# MCISO-S07-V00-CANMain.net
KiCad netlist of a schematic drawn in Altium Designer
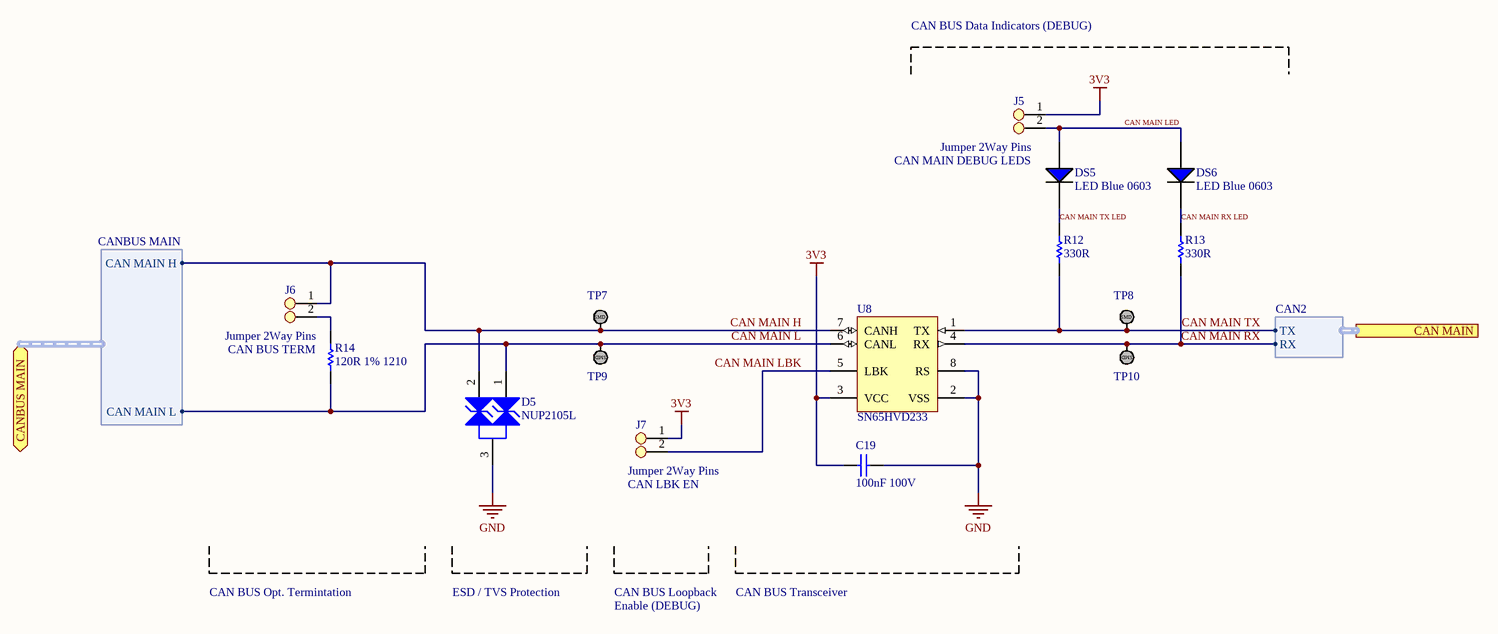
[diagram p0: MCISO-S07-V00-CANMain.SchDoc]

(export (version "E")
  (design (tool "Eeschema 10.0.6"))
  (components
    (comp (ref "C19")
      (value "100nF 100V")
      (footprint "Cap_Ceramic_0603")
      (description "Capacitor, Ceramic, SMD, 100nF, 100V, 5%, X7R, 0603")
      (libsource (lib "StandardCapacitors") (part "100nF 100V 5% X7R 0603"))
    )
    (comp (ref "D5")
      (value "NUP2105L")
      (footprint "NUP2105L")
      (libsource (lib "QUTMS_CANLibrary") (part "NUP2105L"))
    )
    (comp (ref "DS5")
      (value "LED Blue 0603")
      (footprint "LED BLUE 0603")
      (libsource (lib "QUTMS_LEDLibrary") (part "LED BLUE 0603"))
    )
    (comp (ref "DS6")
      (value "LED Blue 0603")
      (footprint "LED BLUE 0603")
      (libsource (lib "QUTMS_LEDLibrary") (part "LED BLUE 0603"))
    )
    (comp (ref "J5")
      (value "Jumper 2Way Pins")
      (footprint "Jumper_2Way_Pin")
      (description "Jumper 2Way Side Pins")
      (libsource (lib "QUTMS_JumperLibrary") (part "Jumper 2Way Side Pins"))
    )
    (comp (ref "J6")
      (value "Jumper 2Way Pins")
      (footprint "Jumper_2Way_Pin")
      (description "Jumper 2Way Side Pins")
      (libsource (lib "QUTMS_JumperLibrary") (part "Jumper 2Way Side Pins"))
    )
    (comp (ref "J7")
      (value "Jumper 2Way Pins")
      (footprint "Jumper_2Way_Pin")
      (description "Jumper 2Way Side Pins")
      (libsource (lib "QUTMS_JumperLibrary") (part "Jumper 2Way Side Pins"))
    )
    (comp (ref "R12")
      (value "330R")
      (footprint "Res_ThinFilm_0603")
      (description "Resistor, SMD, 330R, 0.1W, 5%, 0603")
      (libsource (lib "StandardResistors") (part "330R 5% 0603"))
    )
    (comp (ref "R13")
      (value "330R")
      (footprint "Res_ThinFilm_0603")
      (description "Resistor, SMD, 330R, 0.1W, 5%, 0603")
      (libsource (lib "StandardResistors") (part "330R 5% 0603"))
    )
    (comp (ref "R14")
      (value "120R 1% 1210")
      (footprint "Res_ThinFilm_1210")
      (description "Resistor, SMD, 120R, 0.25W, 1%, 1210")
      (libsource (lib "StandardResistors") (part "120R 1% 1210"))
    )
    (comp (ref "TP7")
      (value "TestPoint_SMD")
      (footprint "TestPointSMD")
      (libsource (lib "StandardTest") (part "TestPoint_SMD"))
    )
    (comp (ref "TP8")
      (value "TestPoint_SMD")
      (footprint "TestPointSMD")
      (libsource (lib "StandardTest") (part "TestPoint_SMD"))
    )
    (comp (ref "TP9")
      (value "TestPoint_SMD")
      (footprint "TestPointSMD")
      (libsource (lib "StandardTest") (part "TestPoint_SMD"))
    )
    (comp (ref "TP10")
      (value "TestPoint_SMD")
      (footprint "TestPointSMD")
      (libsource (lib "StandardTest") (part "TestPoint_SMD"))
    )
    (comp (ref "U8")
      (value "SN65HVD233")
      (footprint "SN65HVD233DR")
      (libsource (lib "QUTMS_CANLibrary") (part "SN65HVD233"))
    )
  )
  (nets
    (net (code "4") (name "/CAN MAIN H") (class "Default")
      (node (ref "D5") (pin "2") (pinfunction "2_2") (pintype "passive"))
      (node (ref "J6") (pin "1") (pinfunction "1_1") (pintype "passive"))
      (node (ref "TP7") (pin "1") (pinfunction "1_1") (pintype "passive"))
      (node (ref "U8") (pin "7") (pinfunction "CANH_7") (pintype "bidirectional"))
    )
    (net (code "5") (name "/CAN MAIN L") (class "Default")
      (node (ref "D5") (pin "1") (pinfunction "1_1") (pintype "passive"))
      (node (ref "R14") (pin "1") (pinfunction "1_1") (pintype "passive"))
      (node (ref "TP9") (pin "1") (pinfunction "1_1") (pintype "passive"))
      (node (ref "U8") (pin "6") (pinfunction "CANL_6") (pintype "bidirectional"))
    )
    (net (code "6") (name "/CAN MAIN LBK") (class "Default")
      (node (ref "J7") (pin "2") (pinfunction "2_2") (pintype "passive"))
      (node (ref "U8") (pin "5") (pinfunction "LBK_5") (pintype "passive"))
    )
    (net (code "7") (name "/CAN MAIN LED") (class "Default")
      (node (ref "DS5") (pin "1") (pinfunction "A_1") (pintype "passive"))
      (node (ref "DS6") (pin "1") (pinfunction "A_1") (pintype "passive"))
      (node (ref "J5") (pin "2") (pinfunction "2_2") (pintype "passive"))
    )
    (net (code "8") (name "/CAN MAIN RX") (class "Default")
      (node (ref "R13") (pin "1") (pinfunction "1_1") (pintype "passive"))
      (node (ref "TP10") (pin "1") (pinfunction "1_1") (pintype "passive"))
      (node (ref "U8") (pin "4") (pinfunction "RX_4") (pintype "output"))
    )
    (net (code "9") (name "/CAN MAIN RX LED") (class "Default")
      (node (ref "DS6") (pin "2") (pinfunction "C_2") (pintype "passive"))
      (node (ref "R13") (pin "2") (pinfunction "2_2") (pintype "passive"))
    )
    (net (code "10") (name "/CAN MAIN TX") (class "Default")
      (node (ref "R12") (pin "1") (pinfunction "1_1") (pintype "passive"))
      (node (ref "TP8") (pin "1") (pinfunction "1_1") (pintype "passive"))
      (node (ref "U8") (pin "1") (pinfunction "TX_1") (pintype "input"))
    )
    (net (code "11") (name "/CAN MAIN TX LED") (class "Default")
      (node (ref "DS5") (pin "2") (pinfunction "C_2") (pintype "passive"))
      (node (ref "R12") (pin "2") (pinfunction "2_2") (pintype "passive"))
    )
    (net (code "14") (name "3V3") (class "Default")
      (node (ref "C19") (pin "2") (pinfunction "2_2") (pintype "passive"))
      (node (ref "J5") (pin "1") (pinfunction "1_1") (pintype "passive"))
      (node (ref "J7") (pin "1") (pinfunction "1_1") (pintype "passive"))
      (node (ref "U8") (pin "3") (pinfunction "VCC_3") (pintype "passive"))
    )
    (net (code "15") (name "GND") (class "Default")
      (node (ref "C19") (pin "1") (pinfunction "1_1") (pintype "passive"))
      (node (ref "D5") (pin "3") (pinfunction "3_3") (pintype "passive"))
      (node (ref "U8") (pin "2") (pinfunction "VSS_2") (pintype "passive"))
      (node (ref "U8") (pin "8") (pinfunction "RS_8") (pintype "passive"))
    )
    (net (code "16") (name "Net-(J6-Pad2)") (class "Default")
      (node (ref "J6") (pin "2") (pinfunction "2_2") (pintype "passive"))
      (node (ref "R14") (pin "2") (pinfunction "2_2") (pintype "passive"))
    )
  )
)
